# M117.net
KiCad netlist of a schematic drawn in EAGLE
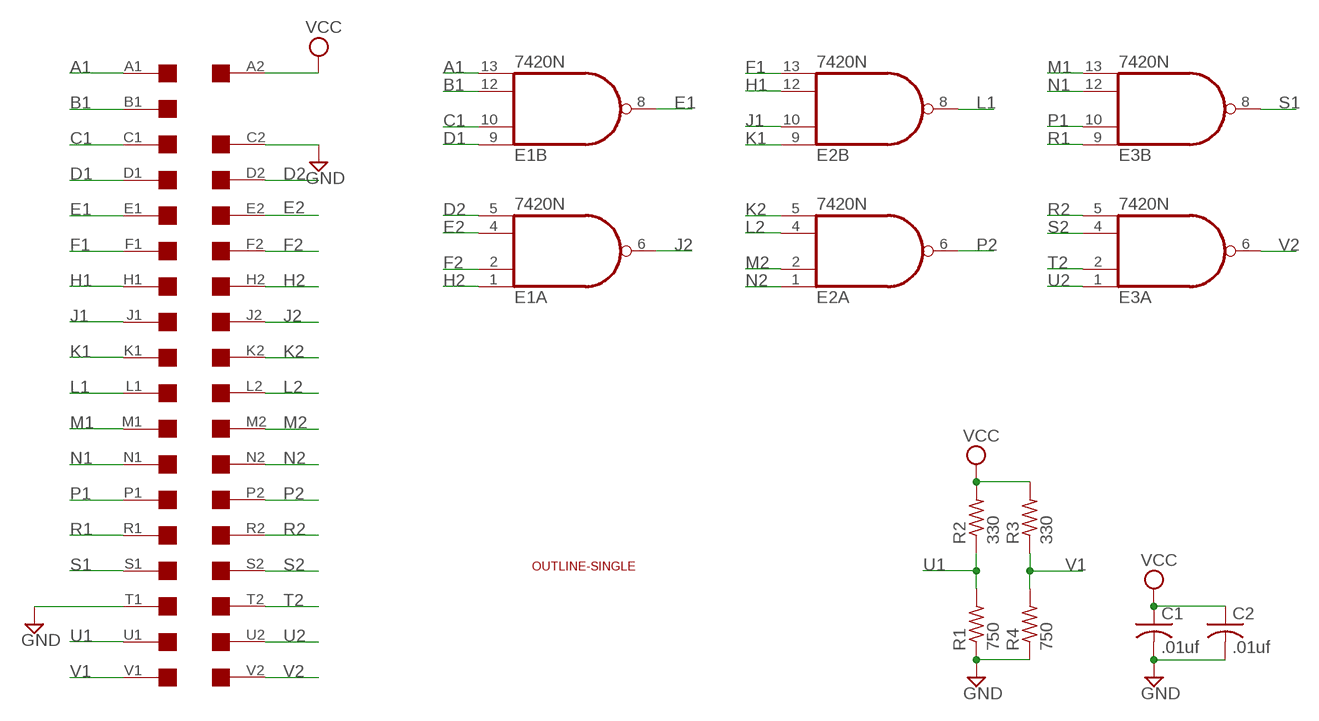
[diagram p0: schematic, sheet 1]

(export (version "E")
  (design (tool "Eeschema 10.0.6"))
  (components
    (comp (ref "C1")
      (value ".01uf")
      (footprint "eagle-import:C050-025X075")
      (libsource (lib "eagle-import") (part "C-US050-025X075"))
    )
    (comp (ref "C2")
      (value ".01uf")
      (footprint "eagle-import:C050-025X075")
      (libsource (lib "eagle-import") (part "C-US050-025X075"))
    )
    (comp (ref "E1")
      (value "7420N")
      (footprint "eagle-import:DIL14")
      (libsource (lib "eagle-import") (part "7420NS"))
    )
    (comp (ref "E2")
      (value "7420N")
      (footprint "eagle-import:DIL14")
      (libsource (lib "eagle-import") (part "7420NS"))
    )
    (comp (ref "E3")
      (value "7420N")
      (footprint "eagle-import:DIL14")
      (libsource (lib "eagle-import") (part "7420NS"))
    )
    (comp (ref "R1")
      (value "750")
      (footprint "eagle-import:0207_10")
      (libsource (lib "eagle-import") (part "R-US_0207/10"))
    )
    (comp (ref "R2")
      (value "330")
      (footprint "eagle-import:0207_10")
      (libsource (lib "eagle-import") (part "R-US_0207/10"))
    )
    (comp (ref "R3")
      (value "330")
      (footprint "eagle-import:0207_10")
      (libsource (lib "eagle-import") (part "R-US_0207/10"))
    )
    (comp (ref "R4")
      (value "750")
      (footprint "eagle-import:0207_10")
      (libsource (lib "eagle-import") (part "R-US_0207/10"))
    )
    (comp (ref "U$1")
      (value "SINGLE")
      (footprint "eagle-import:EDGE-CON2")
      (libsource (lib "eagle-import") (part "SINGLE"))
    )
    (comp (ref "U$4")
      (value "OUTLINE-SINGLE")
      (footprint "eagle-import:SINGLE")
      (libsource (lib "eagle-import") (part "OUTLINE-SINGLE"))
    )
  )
  (nets
    (net (code "1") (name "/A1") (class "Default")
      (node (ref "E1") (pin "13") (pinfunction "I3_13") (pintype "input"))
      (node (ref "U$1") (pin "A1") (pinfunction "1_A1") (pintype "bidirectional"))
    )
    (net (code "2") (name "/B1") (class "Default")
      (node (ref "E1") (pin "12") (pinfunction "I2_12") (pintype "input"))
      (node (ref "U$1") (pin "B1") (pinfunction "1_B1") (pintype "bidirectional"))
    )
    (net (code "3") (name "/C1") (class "Default")
      (node (ref "E1") (pin "10") (pinfunction "I1_10") (pintype "input"))
      (node (ref "U$1") (pin "C1") (pinfunction "1_C1") (pintype "bidirectional"))
    )
    (net (code "4") (name "/D1") (class "Default")
      (node (ref "E1") (pin "9") (pinfunction "I0_9") (pintype "input"))
      (node (ref "U$1") (pin "D1") (pinfunction "1_D1") (pintype "bidirectional"))
    )
    (net (code "5") (name "/D2") (class "Default")
      (node (ref "E1") (pin "5") (pinfunction "I3_5") (pintype "input"))
      (node (ref "U$1") (pin "D2") (pinfunction "1_D2") (pintype "bidirectional"))
    )
    (net (code "6") (name "/E1") (class "Default")
      (node (ref "E1") (pin "8") (pinfunction "O_8") (pintype "output"))
      (node (ref "U$1") (pin "E1") (pinfunction "1_E1") (pintype "bidirectional"))
    )
    (net (code "7") (name "/E2") (class "Default")
      (node (ref "E1") (pin "4") (pinfunction "I2_4") (pintype "input"))
      (node (ref "U$1") (pin "E2") (pinfunction "1_E2") (pintype "bidirectional"))
    )
    (net (code "8") (name "/F1") (class "Default")
      (node (ref "E2") (pin "13") (pinfunction "I3_13") (pintype "input"))
      (node (ref "U$1") (pin "F1") (pinfunction "1_F1") (pintype "bidirectional"))
    )
    (net (code "9") (name "/F2") (class "Default")
      (node (ref "E1") (pin "2") (pinfunction "I1_2") (pintype "input"))
      (node (ref "U$1") (pin "F2") (pinfunction "1_F2") (pintype "bidirectional"))
    )
    (net (code "10") (name "/H1") (class "Default")
      (node (ref "E2") (pin "12") (pinfunction "I2_12") (pintype "input"))
      (node (ref "U$1") (pin "H1") (pinfunction "1_H1") (pintype "bidirectional"))
    )
    (net (code "11") (name "/H2") (class "Default")
      (node (ref "E1") (pin "1") (pinfunction "I0_1") (pintype "input"))
      (node (ref "U$1") (pin "H2") (pinfunction "1_H2") (pintype "bidirectional"))
    )
    (net (code "12") (name "/J1") (class "Default")
      (node (ref "E2") (pin "10") (pinfunction "I1_10") (pintype "input"))
      (node (ref "U$1") (pin "J1") (pinfunction "1_J1") (pintype "bidirectional"))
    )
    (net (code "13") (name "/J2") (class "Default")
      (node (ref "E1") (pin "6") (pinfunction "O_6") (pintype "output"))
      (node (ref "U$1") (pin "J2") (pinfunction "1_J2") (pintype "bidirectional"))
    )
    (net (code "14") (name "/K1") (class "Default")
      (node (ref "E2") (pin "9") (pinfunction "I0_9") (pintype "input"))
      (node (ref "U$1") (pin "K1") (pinfunction "1_K1") (pintype "bidirectional"))
    )
    (net (code "15") (name "/K2") (class "Default")
      (node (ref "E2") (pin "5") (pinfunction "I3_5") (pintype "input"))
      (node (ref "U$1") (pin "K2") (pinfunction "1_K2") (pintype "bidirectional"))
    )
    (net (code "16") (name "/L1") (class "Default")
      (node (ref "E2") (pin "8") (pinfunction "O_8") (pintype "output"))
      (node (ref "U$1") (pin "L1") (pinfunction "1_L1") (pintype "bidirectional"))
    )
    (net (code "17") (name "/L2") (class "Default")
      (node (ref "E2") (pin "4") (pinfunction "I2_4") (pintype "input"))
      (node (ref "U$1") (pin "L2") (pinfunction "1_L2") (pintype "bidirectional"))
    )
    (net (code "18") (name "/M1") (class "Default")
      (node (ref "E3") (pin "13") (pinfunction "I3_13") (pintype "input"))
      (node (ref "U$1") (pin "M1") (pinfunction "1_M1") (pintype "bidirectional"))
    )
    (net (code "19") (name "/M2") (class "Default")
      (node (ref "E2") (pin "2") (pinfunction "I1_2") (pintype "input"))
      (node (ref "U$1") (pin "M2") (pinfunction "1_M2") (pintype "bidirectional"))
    )
    (net (code "20") (name "/N1") (class "Default")
      (node (ref "E3") (pin "12") (pinfunction "I2_12") (pintype "input"))
      (node (ref "U$1") (pin "N1") (pinfunction "1_N1") (pintype "bidirectional"))
    )
    (net (code "21") (name "/N2") (class "Default")
      (node (ref "E2") (pin "1") (pinfunction "I0_1") (pintype "input"))
      (node (ref "U$1") (pin "N2") (pinfunction "1_N2") (pintype "bidirectional"))
    )
    (net (code "22") (name "/P1") (class "Default")
      (node (ref "E3") (pin "10") (pinfunction "I1_10") (pintype "input"))
      (node (ref "U$1") (pin "P1") (pinfunction "1_P1") (pintype "bidirectional"))
    )
    (net (code "23") (name "/P2") (class "Default")
      (node (ref "E2") (pin "6") (pinfunction "O_6") (pintype "output"))
      (node (ref "U$1") (pin "P2") (pinfunction "1_P2") (pintype "bidirectional"))
    )
    (net (code "24") (name "/R1") (class "Default")
      (node (ref "E3") (pin "9") (pinfunction "I0_9") (pintype "input"))
      (node (ref "U$1") (pin "R1") (pinfunction "1_R1") (pintype "bidirectional"))
    )
    (net (code "25") (name "/R2") (class "Default")
      (node (ref "E3") (pin "5") (pinfunction "I3_5") (pintype "input"))
      (node (ref "U$1") (pin "R2") (pinfunction "1_R2") (pintype "bidirectional"))
    )
    (net (code "26") (name "/S1") (class "Default")
      (node (ref "E3") (pin "8") (pinfunction "O_8") (pintype "output"))
      (node (ref "U$1") (pin "S1") (pinfunction "1_S1") (pintype "bidirectional"))
    )
    (net (code "27") (name "/S2") (class "Default")
      (node (ref "E3") (pin "4") (pinfunction "I2_4") (pintype "input"))
      (node (ref "U$1") (pin "S2") (pinfunction "1_S2") (pintype "bidirectional"))
    )
    (net (code "28") (name "/T2") (class "Default")
      (node (ref "E3") (pin "2") (pinfunction "I1_2") (pintype "input"))
      (node (ref "U$1") (pin "T2") (pinfunction "1_T2") (pintype "bidirectional"))
    )
    (net (code "29") (name "/U1") (class "Default")
      (node (ref "R1") (pin "2") (pinfunction "2_2") (pintype "passive"))
      (node (ref "R2") (pin "1") (pinfunction "1_1") (pintype "passive"))
      (node (ref "U$1") (pin "U1") (pinfunction "1_U1") (pintype "bidirectional"))
    )
    (net (code "30") (name "/U2") (class "Default")
      (node (ref "E3") (pin "1") (pinfunction "I0_1") (pintype "input"))
      (node (ref "U$1") (pin "U2") (pinfunction "1_U2") (pintype "bidirectional"))
    )
    (net (code "31") (name "/V1") (class "Default")
      (node (ref "R3") (pin "1") (pinfunction "1_1") (pintype "passive"))
      (node (ref "R4") (pin "2") (pinfunction "2_2") (pintype "passive"))
      (node (ref "U$1") (pin "V1") (pinfunction "1_V1") (pintype "bidirectional"))
    )
    (net (code "32") (name "/V2") (class "Default")
      (node (ref "E3") (pin "6") (pinfunction "O_6") (pintype "output"))
      (node (ref "U$1") (pin "V2") (pinfunction "1_V2") (pintype "bidirectional"))
    )
    (net (code "33") (name "GND") (class "Default")
      (node (ref "C1") (pin "2") (pinfunction "2_2") (pintype "passive"))
      (node (ref "C2") (pin "2") (pinfunction "2_2") (pintype "passive"))
      (node (ref "R1") (pin "1") (pinfunction "1_1") (pintype "passive"))
      (node (ref "R4") (pin "1") (pinfunction "1_1") (pintype "passive"))
      (node (ref "U$1") (pin "C2") (pinfunction "1_C2") (pintype "bidirectional"))
      (node (ref "U$1") (pin "T1") (pinfunction "1_T1") (pintype "bidirectional"))
    )
    (net (code "34") (name "VCC") (class "Default")
      (node (ref "C1") (pin "1") (pinfunction "1_1") (pintype "passive"))
      (node (ref "C2") (pin "1") (pinfunction "1_1") (pintype "passive"))
      (node (ref "R2") (pin "2") (pinfunction "2_2") (pintype "passive"))
      (node (ref "R3") (pin "2") (pinfunction "2_2") (pintype "passive"))
      (node (ref "U$1") (pin "A2") (pinfunction "1_A2") (pintype "bidirectional"))
    )
  )
)
